# jtag-adapter-1-6.net
KiCad netlist of a schematic drawn in EAGLE
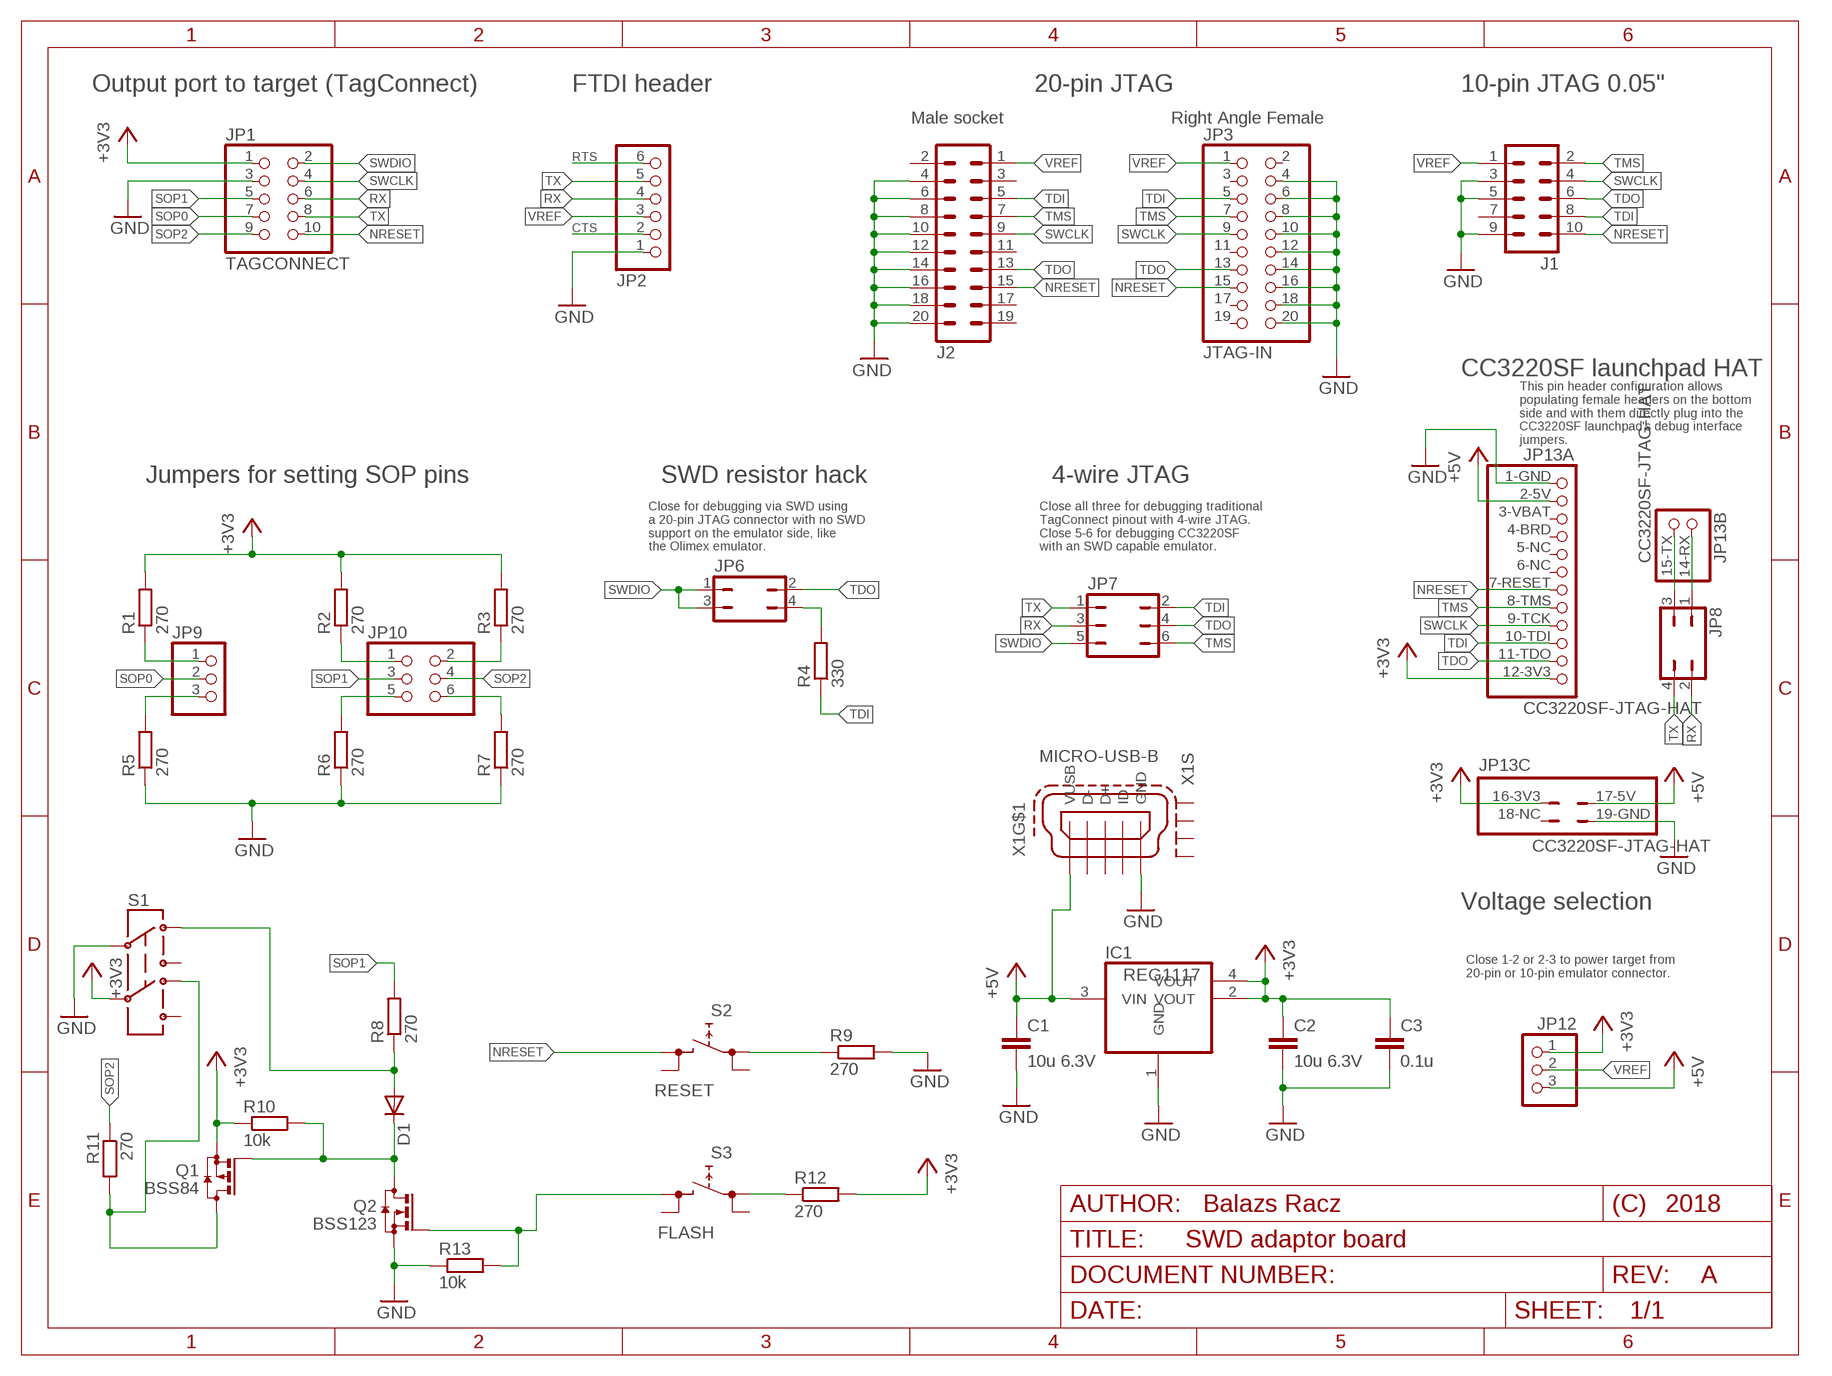
[diagram p0: schematic, sheet 1]

(export (version "E")
  (design (tool "Eeschema 10.0.6"))
  (components
    (comp (ref "C1")
      (value "10u 6.3V")
      (footprint "eagle-import:C0603K")
      (libsource (lib "eagle-import") (part "C-EUC0603K"))
    )
    (comp (ref "C2")
      (value "10u 6.3V")
      (footprint "eagle-import:C0603K")
      (libsource (lib "eagle-import") (part "C-EUC0603K"))
    )
    (comp (ref "C3")
      (value "0.1u")
      (footprint "eagle-import:C0603K")
      (libsource (lib "eagle-import") (part "C-EUC0603K"))
    )
    (comp (ref "D1")
      (value "DIODE-MINIMELF")
      (footprint "eagle-import:MINIMELF")
      (libsource (lib "eagle-import") (part "DIODE-MINIMELF"))
    )
    (comp (ref "IC1")
      (value "REG1117")
      (footprint "eagle-import:SOT223")
      (libsource (lib "eagle-import") (part "REG1117"))
    )
    (comp (ref "J1")
      (value "MA05-2_0.05X0.05")
      (footprint "eagle-import:MA05-2_0.05_X_0.05")
      (libsource (lib "eagle-import") (part "MA05-2_0.05X0.05"))
    )
    (comp (ref "J2")
      (value "MA10-2S")
      (footprint "eagle-import:MA10-2-SHROUDED")
      (libsource (lib "eagle-import") (part "MA10-2S"))
    )
    (comp (ref "JP1")
      (value "TAGCONNECT")
      (footprint "eagle-import:CON10M")
      (libsource (lib "eagle-import") (part "PINHD-2X5CN"))
    )
    (comp (ref "JP2")
      (value "PINHD-1X6")
      (footprint "eagle-import:1X06")
      (libsource (lib "eagle-import") (part "PINHD-1X6"))
    )
    (comp (ref "JP3")
      (value "JTAG-IN")
      (footprint "eagle-import:2X10_90")
      (libsource (lib "eagle-import") (part "PINHD-2X10/90"))
    )
    (comp (ref "JP6")
      (value "JP2Q")
      (footprint "eagle-import:JP2Q")
      (libsource (lib "eagle-import") (part "JP2Q"))
    )
    (comp (ref "JP7")
      (value "JP3Q")
      (footprint "eagle-import:JP3Q")
      (libsource (lib "eagle-import") (part "JP3Q"))
    )
    (comp (ref "JP8")
      (value "JP2Q")
      (footprint "eagle-import:JP2Q")
      (libsource (lib "eagle-import") (part "JP2Q"))
    )
    (comp (ref "JP9")
      (value "PINHD-1X3")
      (footprint "eagle-import:1X03")
      (libsource (lib "eagle-import") (part "PINHD-1X3"))
    )
    (comp (ref "JP10")
      (value "PINHD-2X3")
      (footprint "eagle-import:2X03")
      (libsource (lib "eagle-import") (part "PINHD-2X3"))
    )
    (comp (ref "JP12")
      (value "PINHD-1X3")
      (footprint "eagle-import:1X03")
      (libsource (lib "eagle-import") (part "PINHD-1X3"))
    )
    (comp (ref "JP13")
      (value "CC3220SF-JTAG-HAT")
      (footprint "eagle-import:JTAG-LAUNCHPAD-3220SF")
      (libsource (lib "eagle-import") (part "CC3220SF-JTAG-HAT"))
    )
    (comp (ref "Q1")
      (value "BSS84")
      (footprint "eagle-import:SOT23")
      (libsource (lib "eagle-import") (part "BSS84"))
    )
    (comp (ref "Q2")
      (value "BSS123")
      (footprint "eagle-import:SOT23")
      (libsource (lib "eagle-import") (part "BSS123"))
    )
    (comp (ref "R1")
      (value "270")
      (footprint "eagle-import:R0805")
      (libsource (lib "eagle-import") (part "R-EU_R0805"))
    )
    (comp (ref "R2")
      (value "270")
      (footprint "eagle-import:R0805")
      (libsource (lib "eagle-import") (part "R-EU_R0805"))
    )
    (comp (ref "R3")
      (value "270")
      (footprint "eagle-import:R0805")
      (libsource (lib "eagle-import") (part "R-EU_R0805"))
    )
    (comp (ref "R4")
      (value "330")
      (footprint "eagle-import:R0805")
      (libsource (lib "eagle-import") (part "R-EU_R0805"))
    )
    (comp (ref "R5")
      (value "270")
      (footprint "eagle-import:R0805")
      (libsource (lib "eagle-import") (part "R-EU_R0805"))
    )
    (comp (ref "R6")
      (value "270")
      (footprint "eagle-import:R0805")
      (libsource (lib "eagle-import") (part "R-EU_R0805"))
    )
    (comp (ref "R7")
      (value "270")
      (footprint "eagle-import:R0805")
      (libsource (lib "eagle-import") (part "R-EU_R0805"))
    )
    (comp (ref "R8")
      (value "270")
      (footprint "eagle-import:R0805")
      (libsource (lib "eagle-import") (part "R-EU_R0805"))
    )
    (comp (ref "R9")
      (value "270")
      (footprint "eagle-import:R0805")
      (libsource (lib "eagle-import") (part "R-EU_R0805"))
    )
    (comp (ref "R10")
      (value "10k")
      (footprint "eagle-import:R0805")
      (libsource (lib "eagle-import") (part "R-EU_R0805"))
    )
    (comp (ref "R11")
      (value "270")
      (footprint "eagle-import:R0805")
      (libsource (lib "eagle-import") (part "R-EU_R0805"))
    )
    (comp (ref "R12")
      (value "270")
      (footprint "eagle-import:R0805")
      (libsource (lib "eagle-import") (part "R-EU_R0805"))
    )
    (comp (ref "R13")
      (value "10k")
      (footprint "eagle-import:R0805")
      (libsource (lib "eagle-import") (part "R-EU_R0805"))
    )
    (comp (ref "S1")
      (value "SWITCH-DPDTJS202011CQN")
      (footprint "eagle-import:DPDT-2.5X3.2MM")
      (libsource (lib "eagle-import") (part "SWITCH-DPDTJS202011CQN"))
    )
    (comp (ref "S2")
      (value "RESET")
      (footprint "eagle-import:TACTSW-6X6")
      (libsource (lib "eagle-import") (part "TACTSW-6X6S"))
    )
    (comp (ref "S3")
      (value "FLASH")
      (footprint "eagle-import:TACTSW-6X6")
      (libsource (lib "eagle-import") (part "TACTSW-6X6S"))
    )
    (comp (ref "X1")
      (value "MICRO-USB-B")
      (footprint "eagle-import:MICRO-B-PAC")
      (libsource (lib "eagle-import") (part "MICRO-USB-B"))
    )
  )
  (nets
    (net (code "1") (name "+3V3") (class "Default")
      (node (ref "C2") (pin "1") (pinfunction "1_1") (pintype "passive"))
      (node (ref "C3") (pin "1") (pinfunction "1_1") (pintype "passive"))
      (node (ref "IC1") (pin "2") (pinfunction "VOUT_2") (pintype "output"))
      (node (ref "IC1") (pin "4") (pinfunction "VOUT_4") (pintype "output"))
      (node (ref "JP1") (pin "1") (pinfunction "1_1") (pintype "passive"))
      (node (ref "JP12") (pin "1") (pinfunction "1_1") (pintype "passive"))
      (node (ref "JP13") (pin "12-3V3") (pinfunction "12_12-3V3") (pintype "passive"))
      (node (ref "JP13") (pin "16-3V3") (pinfunction "1_16-3V3") (pintype "passive"))
      (node (ref "Q1") (pin "2") (pinfunction "S_2") (pintype "passive"))
      (node (ref "R1") (pin "2") (pinfunction "2_2") (pintype "passive"))
      (node (ref "R10") (pin "1") (pinfunction "1_1") (pintype "passive"))
      (node (ref "R12") (pin "2") (pinfunction "2_2") (pintype "passive"))
      (node (ref "R2") (pin "2") (pinfunction "2_2") (pintype "passive"))
      (node (ref "R3") (pin "2") (pinfunction "2_2") (pintype "passive"))
      (node (ref "S1") (pin "5") (pinfunction "2C_5") (pintype "bidirectional"))
    )
    (net (code "2") (name "+5V") (class "Default")
      (node (ref "C1") (pin "1") (pinfunction "1_1") (pintype "passive"))
      (node (ref "IC1") (pin "3") (pinfunction "VIN_3") (pintype "input"))
      (node (ref "JP12") (pin "3") (pinfunction "3_3") (pintype "passive"))
      (node (ref "JP13") (pin "17-5V") (pinfunction "2_17-5V") (pintype "passive"))
      (node (ref "JP13") (pin "2-5V") (pinfunction "2_2-5V") (pintype "passive"))
      (node (ref "X1") (pin "1") (pinfunction "VUSB_1") (pintype "passive"))
    )
    (net (code "3") (name "/CTS") (class "Default")
      (node (ref "JP2") (pin "2") (pinfunction "2_2") (pintype "passive"))
    )
    (net (code "4") (name "/RTS") (class "Default")
      (node (ref "JP2") (pin "6") (pinfunction "6_6") (pintype "passive"))
    )
    (net (code "5") (name "GND") (class "Default")
      (node (ref "C1") (pin "2") (pinfunction "2_2") (pintype "passive"))
      (node (ref "C2") (pin "2") (pinfunction "2_2") (pintype "passive"))
      (node (ref "C3") (pin "2") (pinfunction "2_2") (pintype "passive"))
      (node (ref "IC1") (pin "1") (pinfunction "GND_1") (pintype "power_in"))
      (node (ref "J1") (pin "3") (pinfunction "3_3") (pintype "passive"))
      (node (ref "J1") (pin "5") (pinfunction "5_5") (pintype "passive"))
      (node (ref "J1") (pin "9") (pinfunction "9_9") (pintype "passive"))
      (node (ref "J2") (pin "10") (pinfunction "10_10") (pintype "passive"))
      (node (ref "J2") (pin "12") (pinfunction "12_12") (pintype "passive"))
      (node (ref "J2") (pin "14") (pinfunction "14_14") (pintype "passive"))
      (node (ref "J2") (pin "16") (pinfunction "16_16") (pintype "passive"))
      (node (ref "J2") (pin "18") (pinfunction "18_18") (pintype "passive"))
      (node (ref "J2") (pin "20") (pinfunction "20_20") (pintype "passive"))
      (node (ref "J2") (pin "4") (pinfunction "4_4") (pintype "passive"))
      (node (ref "J2") (pin "6") (pinfunction "6_6") (pintype "passive"))
      (node (ref "J2") (pin "8") (pinfunction "8_8") (pintype "passive"))
      (node (ref "JP1") (pin "3") (pinfunction "3_3") (pintype "passive"))
      (node (ref "JP13") (pin "1-GND") (pinfunction "1_1-GND") (pintype "passive"))
      (node (ref "JP13") (pin "19-GND") (pinfunction "4_19-GND") (pintype "passive"))
      (node (ref "JP2") (pin "1") (pinfunction "1_1") (pintype "passive"))
      (node (ref "JP3") (pin "10") (pinfunction "10_10") (pintype "passive"))
      (node (ref "JP3") (pin "12") (pinfunction "12_12") (pintype "passive"))
      (node (ref "JP3") (pin "14") (pinfunction "14_14") (pintype "passive"))
      (node (ref "JP3") (pin "16") (pinfunction "16_16") (pintype "passive"))
      (node (ref "JP3") (pin "18") (pinfunction "18_18") (pintype "passive"))
      (node (ref "JP3") (pin "20") (pinfunction "20_20") (pintype "passive"))
      (node (ref "JP3") (pin "4") (pinfunction "4_4") (pintype "passive"))
      (node (ref "JP3") (pin "6") (pinfunction "6_6") (pintype "passive"))
      (node (ref "JP3") (pin "8") (pinfunction "8_8") (pintype "passive"))
      (node (ref "Q2") (pin "2") (pinfunction "S_2") (pintype "passive"))
      (node (ref "R13") (pin "1") (pinfunction "1_1") (pintype "passive"))
      (node (ref "R5") (pin "1") (pinfunction "1_1") (pintype "passive"))
      (node (ref "R6") (pin "1") (pinfunction "1_1") (pintype "passive"))
      (node (ref "R7") (pin "1") (pinfunction "1_1") (pintype "passive"))
      (node (ref "R9") (pin "2") (pinfunction "2_2") (pintype "passive"))
      (node (ref "S1") (pin "2") (pinfunction "1C_2") (pintype "bidirectional"))
      (node (ref "X1") (pin "5") (pinfunction "GND_5") (pintype "passive"))
    )
    (net (code "6") (name "NRESET") (class "Default")
      (node (ref "J1") (pin "10") (pinfunction "10_10") (pintype "passive"))
      (node (ref "J2") (pin "15") (pinfunction "15_15") (pintype "passive"))
      (node (ref "JP1") (pin "10") (pinfunction "10_10") (pintype "passive"))
      (node (ref "JP13") (pin "7-RESET") (pinfunction "7_7-RESET") (pintype "passive"))
      (node (ref "JP3") (pin "15") (pinfunction "15_15") (pintype "passive"))
      (node (ref "S2") (pin "3") (pinfunction "2.1_3") (pintype "passive"))
    )
    (net (code "7") (name "Net-(JP6-Pad4)") (class "Default")
      (node (ref "JP6") (pin "4") (pinfunction "4_4") (pintype "passive"))
      (node (ref "R4") (pin "2") (pinfunction "2_2") (pintype "passive"))
    )
    (net (code "8") (name "Net-(JP9-Pad1)") (class "Default")
      (node (ref "JP9") (pin "1") (pinfunction "1_1") (pintype "passive"))
      (node (ref "R1") (pin "1") (pinfunction "1_1") (pintype "passive"))
    )
    (net (code "9") (name "Net-(JP9-Pad3)") (class "Default")
      (node (ref "JP9") (pin "3") (pinfunction "3_3") (pintype "passive"))
      (node (ref "R5") (pin "2") (pinfunction "2_2") (pintype "passive"))
    )
    (net (code "10") (name "Net-(JP10-Pad1)") (class "Default")
      (node (ref "JP10") (pin "1") (pinfunction "1_1") (pintype "passive"))
      (node (ref "R2") (pin "1") (pinfunction "1_1") (pintype "passive"))
    )
    (net (code "11") (name "Net-(JP10-Pad2)") (class "Default")
      (node (ref "JP10") (pin "2") (pinfunction "2_2") (pintype "passive"))
      (node (ref "R3") (pin "1") (pinfunction "1_1") (pintype "passive"))
    )
    (net (code "12") (name "Net-(JP10-Pad5)") (class "Default")
      (node (ref "JP10") (pin "5") (pinfunction "5_5") (pintype "passive"))
      (node (ref "R6") (pin "2") (pinfunction "2_2") (pintype "passive"))
    )
    (net (code "13") (name "Net-(JP10-Pad6)") (class "Default")
      (node (ref "JP10") (pin "6") (pinfunction "6_6") (pintype "passive"))
      (node (ref "R7") (pin "2") (pinfunction "2_2") (pintype "passive"))
    )
    (net (code "14") (name "Net-(JP13B-1)") (class "Default")
      (node (ref "JP13") (pin "14-RX") (pinfunction "1_14-RX") (pintype "passive"))
      (node (ref "JP8") (pin "1") (pinfunction "1_1") (pintype "passive"))
    )
    (net (code "15") (name "Net-(JP13B-2)") (class "Default")
      (node (ref "JP13") (pin "15-TX") (pinfunction "2_15-TX") (pintype "passive"))
      (node (ref "JP8") (pin "3") (pinfunction "3_3") (pintype "passive"))
    )
    (net (code "16") (name "Net-(Q1-D)") (class "Default")
      (node (ref "Q1") (pin "3") (pinfunction "D_3") (pintype "passive"))
      (node (ref "R11") (pin "2") (pinfunction "2_2") (pintype "passive"))
      (node (ref "S1") (pin "4") (pinfunction "2A_4") (pintype "bidirectional"))
    )
    (net (code "17") (name "Net-(Q1-G)") (class "Default")
      (node (ref "D1") (pin "C") (pinfunction "C_C") (pintype "passive"))
      (node (ref "Q1") (pin "1") (pinfunction "G_1") (pintype "passive"))
      (node (ref "Q2") (pin "3") (pinfunction "D_3") (pintype "passive"))
      (node (ref "R10") (pin "2") (pinfunction "2_2") (pintype "passive"))
    )
    (net (code "18") (name "Net-(Q2-G)") (class "Default")
      (node (ref "Q2") (pin "1") (pinfunction "G_1") (pintype "passive"))
      (node (ref "R13") (pin "2") (pinfunction "2_2") (pintype "passive"))
      (node (ref "S3") (pin "3") (pinfunction "2.1_3") (pintype "passive"))
    )
    (net (code "19") (name "Net-(S1-1A)") (class "Default")
      (node (ref "D1") (pin "A") (pinfunction "A_A") (pintype "passive"))
      (node (ref "R8") (pin "1") (pinfunction "1_1") (pintype "passive"))
      (node (ref "S1") (pin "1") (pinfunction "1A_1") (pintype "bidirectional"))
    )
    (net (code "20") (name "Net-(S2-1.1)") (class "Default")
      (node (ref "R9") (pin "1") (pinfunction "1_1") (pintype "passive"))
      (node (ref "S2") (pin "1") (pinfunction "1.1_1") (pintype "passive"))
    )
    (net (code "21") (name "Net-(S3-1.1)") (class "Default")
      (node (ref "R12") (pin "1") (pinfunction "1_1") (pintype "passive"))
      (node (ref "S3") (pin "1") (pinfunction "1.1_1") (pintype "passive"))
    )
    (net (code "22") (name "RX") (class "Default")
      (node (ref "JP1") (pin "6") (pinfunction "6_6") (pintype "passive"))
      (node (ref "JP2") (pin "4") (pinfunction "4_4") (pintype "passive"))
      (node (ref "JP7") (pin "3") (pinfunction "3_3") (pintype "passive"))
      (node (ref "JP8") (pin "2") (pinfunction "2_2") (pintype "passive"))
    )
    (net (code "23") (name "SOP0") (class "Default")
      (node (ref "JP1") (pin "7") (pinfunction "7_7") (pintype "passive"))
      (node (ref "JP9") (pin "2") (pinfunction "2_2") (pintype "passive"))
    )
    (net (code "24") (name "SOP1") (class "Default")
      (node (ref "JP1") (pin "5") (pinfunction "5_5") (pintype "passive"))
      (node (ref "JP10") (pin "3") (pinfunction "3_3") (pintype "passive"))
      (node (ref "R8") (pin "2") (pinfunction "2_2") (pintype "passive"))
    )
    (net (code "25") (name "SOP2") (class "Default")
      (node (ref "JP1") (pin "9") (pinfunction "9_9") (pintype "passive"))
      (node (ref "JP10") (pin "4") (pinfunction "4_4") (pintype "passive"))
      (node (ref "R11") (pin "1") (pinfunction "1_1") (pintype "passive"))
    )
    (net (code "26") (name "SWCLK") (class "Default")
      (node (ref "J1") (pin "4") (pinfunction "4_4") (pintype "passive"))
      (node (ref "J2") (pin "9") (pinfunction "9_9") (pintype "passive"))
      (node (ref "JP1") (pin "4") (pinfunction "4_4") (pintype "passive"))
      (node (ref "JP13") (pin "9-TCK") (pinfunction "9_9-TCK") (pintype "passive"))
      (node (ref "JP3") (pin "9") (pinfunction "9_9") (pintype "passive"))
    )
    (net (code "27") (name "SWDIO") (class "Default")
      (node (ref "JP1") (pin "2") (pinfunction "2_2") (pintype "passive"))
      (node (ref "JP6") (pin "1") (pinfunction "1_1") (pintype "passive"))
      (node (ref "JP6") (pin "3") (pinfunction "3_3") (pintype "passive"))
      (node (ref "JP7") (pin "5") (pinfunction "5_5") (pintype "passive"))
    )
    (net (code "28") (name "TDI") (class "Default")
      (node (ref "J1") (pin "8") (pinfunction "8_8") (pintype "passive"))
      (node (ref "J2") (pin "5") (pinfunction "5_5") (pintype "passive"))
      (node (ref "JP13") (pin "10-TDI") (pinfunction "10_10-TDI") (pintype "passive"))
      (node (ref "JP3") (pin "5") (pinfunction "5_5") (pintype "passive"))
      (node (ref "JP7") (pin "2") (pinfunction "2_2") (pintype "passive"))
      (node (ref "R4") (pin "1") (pinfunction "1_1") (pintype "passive"))
    )
    (net (code "29") (name "TDO") (class "Default")
      (node (ref "J1") (pin "6") (pinfunction "6_6") (pintype "passive"))
      (node (ref "J2") (pin "13") (pinfunction "13_13") (pintype "passive"))
      (node (ref "JP13") (pin "11-TDO") (pinfunction "11_11-TDO") (pintype "passive"))
      (node (ref "JP3") (pin "13") (pinfunction "13_13") (pintype "passive"))
      (node (ref "JP6") (pin "2") (pinfunction "2_2") (pintype "passive"))
      (node (ref "JP7") (pin "4") (pinfunction "4_4") (pintype "passive"))
    )
    (net (code "30") (name "TMS") (class "Default")
      (node (ref "J1") (pin "2") (pinfunction "2_2") (pintype "passive"))
      (node (ref "J2") (pin "7") (pinfunction "7_7") (pintype "passive"))
      (node (ref "JP13") (pin "8-TMS") (pinfunction "8_8-TMS") (pintype "passive"))
      (node (ref "JP3") (pin "7") (pinfunction "7_7") (pintype "passive"))
      (node (ref "JP7") (pin "6") (pinfunction "6_6") (pintype "passive"))
    )
    (net (code "31") (name "TX") (class "Default")
      (node (ref "JP1") (pin "8") (pinfunction "8_8") (pintype "passive"))
      (node (ref "JP2") (pin "5") (pinfunction "5_5") (pintype "passive"))
      (node (ref "JP7") (pin "1") (pinfunction "1_1") (pintype "passive"))
      (node (ref "JP8") (pin "4") (pinfunction "4_4") (pintype "passive"))
    )
    (net (code "32") (name "VREF") (class "Default")
      (node (ref "J1") (pin "1") (pinfunction "1_1") (pintype "passive"))
      (node (ref "J2") (pin "1") (pinfunction "1_1") (pintype "passive"))
      (node (ref "JP12") (pin "2") (pinfunction "2_2") (pintype "passive"))
      (node (ref "JP2") (pin "3") (pinfunction "3_3") (pintype "passive"))
      (node (ref "JP3") (pin "1") (pinfunction "1_1") (pintype "passive"))
    )
    (net (code "33") (name "unconnected-(J1-Pad7)") (class "Default")
      (node (ref "J1") (pin "7") (pinfunction "7_7") (pintype "passive"))
    )
    (net (code "34") (name "unconnected-(J2-Pad2)") (class "Default")
      (node (ref "J2") (pin "2") (pinfunction "2_2") (pintype "passive"))
    )
    (net (code "35") (name "unconnected-(J2-Pad3)") (class "Default")
      (node (ref "J2") (pin "3") (pinfunction "3_3") (pintype "passive"))
    )
    (net (code "36") (name "unconnected-(J2-Pad11)") (class "Default")
      (node (ref "J2") (pin "11") (pinfunction "11_11") (pintype "passive"))
    )
    (net (code "37") (name "unconnected-(J2-Pad17)") (class "Default")
      (node (ref "J2") (pin "17") (pinfunction "17_17") (pintype "passive"))
    )
    (net (code "38") (name "unconnected-(J2-Pad19)") (class "Default")
      (node (ref "J2") (pin "19") (pinfunction "19_19") (pintype "passive"))
    )
    (net (code "39") (name "unconnected-(JP3-Pad2)") (class "Default")
      (node (ref "JP3") (pin "2") (pinfunction "2_2") (pintype "passive"))
    )
    (net (code "40") (name "unconnected-(JP3-Pad3)") (class "Default")
      (node (ref "JP3") (pin "3") (pinfunction "3_3") (pintype "passive"))
    )
    (net (code "41") (name "unconnected-(JP3-Pad11)") (class "Default")
      (node (ref "JP3") (pin "11") (pinfunction "11_11") (pintype "passive"))
    )
    (net (code "42") (name "unconnected-(JP3-Pad17)") (class "Default")
      (node (ref "JP3") (pin "17") (pinfunction "17_17") (pintype "passive"))
    )
    (net (code "43") (name "unconnected-(JP3-Pad19)") (class "Default")
      (node (ref "JP3") (pin "19") (pinfunction "19_19") (pintype "passive"))
    )
    (net (code "44") (name "unconnected-(JP13A-3-Pad3-VBAT)") (class "Default")
      (node (ref "JP13") (pin "3-VBAT") (pinfunction "3_3-VBAT") (pintype "passive"))
    )
    (net (code "45") (name "unconnected-(JP13A-4-Pad4-BRD)") (class "Default")
      (node (ref "JP13") (pin "4-BRD") (pinfunction "4_4-BRD") (pintype "passive"))
    )
    (net (code "46") (name "unconnected-(JP13A-5-Pad5-NC)") (class "Default")
      (node (ref "JP13") (pin "5-NC") (pinfunction "5_5-NC") (pintype "passive"))
    )
    (net (code "47") (name "unconnected-(JP13A-6-Pad6-NC)") (class "Default")
      (node (ref "JP13") (pin "6-NC") (pinfunction "6_6-NC") (pintype "passive"))
    )
    (net (code "48") (name "unconnected-(JP13C-3-Pad18-NC)") (class "Default")
      (node (ref "JP13") (pin "18-NC") (pinfunction "3_18-NC") (pintype "passive"))
    )
    (net (code "49") (name "unconnected-(S1-1B-Pad3)") (class "Default")
      (node (ref "S1") (pin "3") (pinfunction "1B_3") (pintype "bidirectional"))
    )
    (net (code "50") (name "unconnected-(S1-2B-Pad6)") (class "Default")
      (node (ref "S1") (pin "6") (pinfunction "2B_6") (pintype "bidirectional"))
    )
    (net (code "51") (name "unconnected-(S2-1.2-Pad2)") (class "Default")
      (node (ref "S2") (pin "2") (pinfunction "1.2_2") (pintype "passive"))
    )
    (net (code "52") (name "unconnected-(S2-2.2-Pad4)") (class "Default")
      (node (ref "S2") (pin "4") (pinfunction "2.2_4") (pintype "passive"))
    )
    (net (code "53") (name "unconnected-(S3-1.2-Pad2)") (class "Default")
      (node (ref "S3") (pin "2") (pinfunction "1.2_2") (pintype "passive"))
    )
    (net (code "54") (name "unconnected-(S3-2.2-Pad4)") (class "Default")
      (node (ref "S3") (pin "4") (pinfunction "2.2_4") (pintype "passive"))
    )
    (net (code "55") (name "unconnected-(X1A-D+-Pad3)") (class "Default")
      (node (ref "X1") (pin "3") (pinfunction "D+_3") (pintype "passive"))
    )
    (net (code "56") (name "unconnected-(X1A-D--Pad2)") (class "Default")
      (node (ref "X1") (pin "2") (pinfunction "D-_2") (pintype "passive"))
    )
    (net (code "57") (name "unconnected-(X1A-ID-Pad4)") (class "Default")
      (node (ref "X1") (pin "4") (pinfunction "ID_4") (pintype "passive"))
    )
    (net (code "58") (name "unconnected-(X1B-S1-PadM1)") (class "Default")
      (node (ref "X1") (pin "M1") (pinfunction "S1_M1") (pintype "passive"))
    )
    (net (code "59") (name "unconnected-(X1B-S2-PadM2)") (class "Default")
      (node (ref "X1") (pin "M2") (pinfunction "S2_M2") (pintype "passive"))
    )
    (net (code "60") (name "unconnected-(X1B-S3-PadM3)") (class "Default")
      (node (ref "X1") (pin "M3") (pinfunction "S3_M3") (pintype "passive"))
    )
    (net (code "61") (name "unconnected-(X1B-S4-PadM4)") (class "Default")
      (node (ref "X1") (pin "M4") (pinfunction "S4_M4") (pintype "passive"))
    )
  )
)
